# ui_xte_usb.net
KiCad netlist of a schematic drawn in Altium Designer
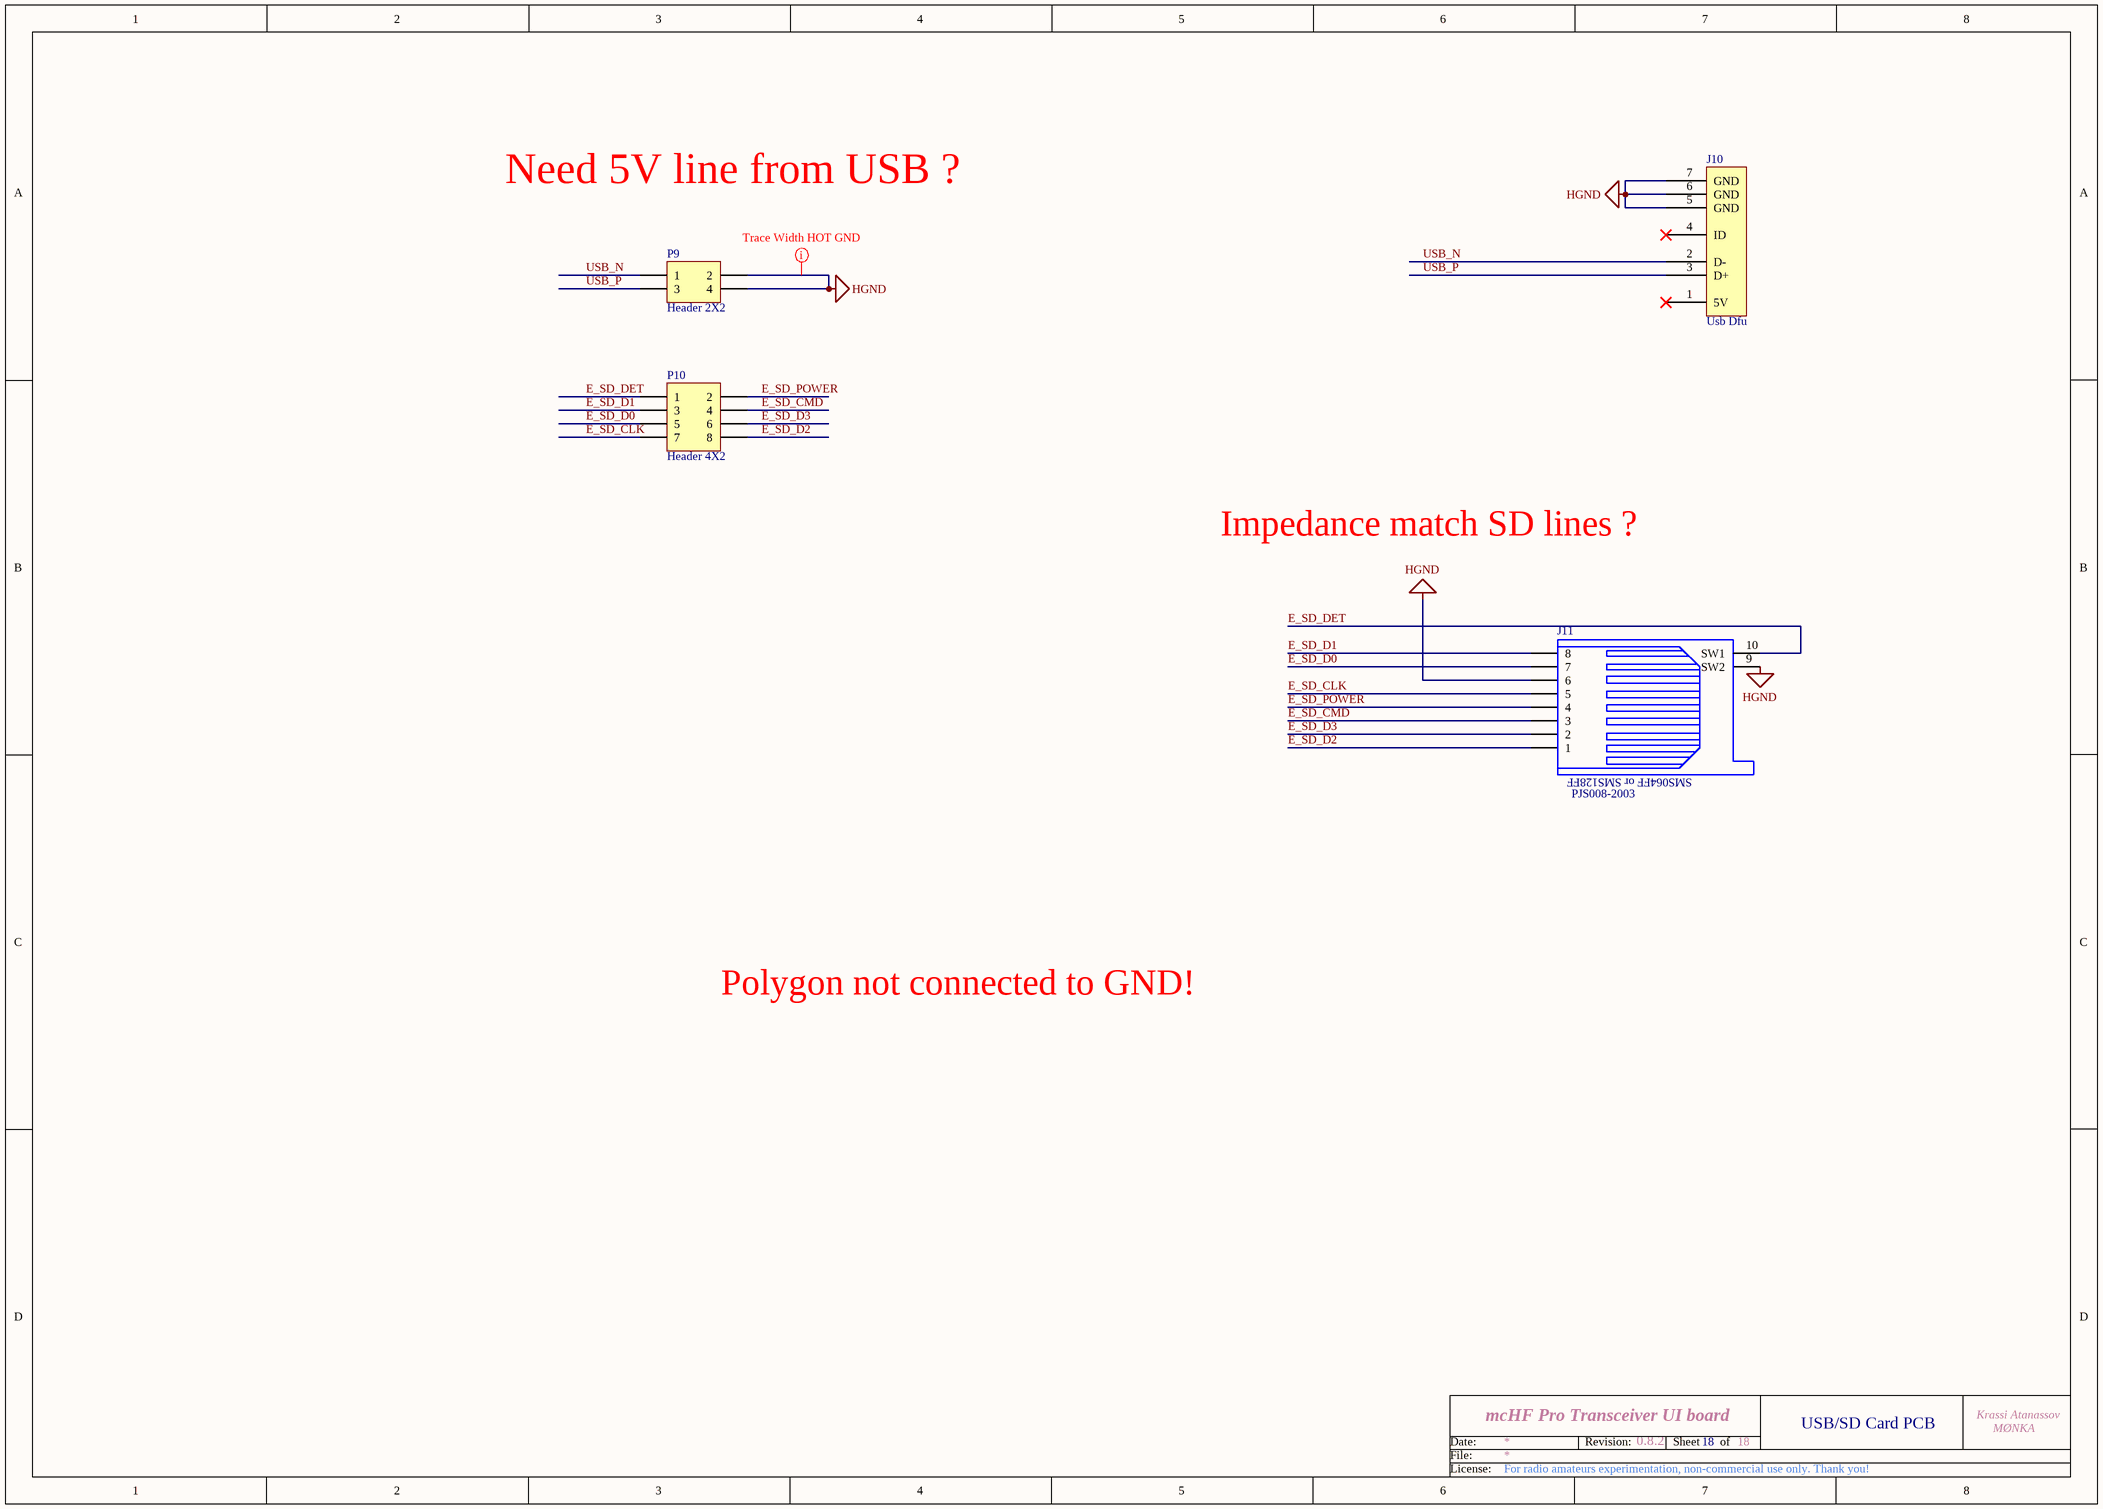
[diagram p0: ui_xte_usb.SchDoc]

(export (version "E")
  (design (tool "Eeschema 10.0.6"))
  (components
    (comp (ref "J10")
      (value "Usb Dfu")
      (footprint "MINI_USB_B_SMD")
      (description "Mini USB connector")
      (libsource (lib "mcHF_ui") (part "MINI_USB_B"))
    )
    (comp (ref "J11")
      (value "PJS008-2003")
      (footprint "PJS008-2003-1")
      (description "Memory Card Connectors MicroSD Card Conn Revrs Mnt Push-Push")
      (libsource (lib "MCD_TOOLS") (part "microSD-PJS008-2003"))
    )
    (comp (ref "P9")
      (value "Header 2X2")
      (footprint "HDR2X2R")
      (description "Header, 2-Pin, Dual row")
      (fields (field (name "PUBLISHER") "Altium Limited"))
      (libsource (lib "__ui") (part "Header 2X2"))
    )
    (comp (ref "P10")
      (value "Header 4X2")
      (footprint "HDR2X4R")
      (description "Header, 4-Pin, Dual row")
      (fields (field (name "PUBLISHER") "Altium Limited"))
      (libsource (lib "__ui") (part "Header 4X2"))
    )
  )
  (nets
    (net (code "1") (name "/E_SD_CLK") (class "Default")
      (node (ref "J11") (pin "5") (pinfunction "5_5") (pintype "passive"))
      (node (ref "P10") (pin "7") (pinfunction "7_7") (pintype "passive"))
    )
    (net (code "2") (name "/E_SD_CMD") (class "Default")
      (node (ref "J11") (pin "3") (pinfunction "3_3") (pintype "passive"))
      (node (ref "P10") (pin "4") (pinfunction "4_4") (pintype "passive"))
    )
    (net (code "3") (name "/E_SD_D0") (class "Default")
      (node (ref "J11") (pin "7") (pinfunction "7_7") (pintype "passive"))
      (node (ref "P10") (pin "5") (pinfunction "5_5") (pintype "passive"))
    )
    (net (code "4") (name "/E_SD_D1") (class "Default")
      (node (ref "J11") (pin "8") (pinfunction "8_8") (pintype "passive"))
      (node (ref "P10") (pin "3") (pinfunction "3_3") (pintype "passive"))
    )
    (net (code "5") (name "/E_SD_D2") (class "Default")
      (node (ref "J11") (pin "1") (pinfunction "1_1") (pintype "passive"))
      (node (ref "P10") (pin "8") (pinfunction "8_8") (pintype "passive"))
    )
    (net (code "6") (name "/E_SD_D3") (class "Default")
      (node (ref "J11") (pin "2") (pinfunction "2_2") (pintype "passive"))
      (node (ref "P10") (pin "6") (pinfunction "6_6") (pintype "passive"))
    )
    (net (code "7") (name "/E_SD_DET") (class "Default")
      (node (ref "J11") (pin "10") (pinfunction "SW1_10") (pintype "passive"))
      (node (ref "P10") (pin "1") (pinfunction "1_1") (pintype "passive"))
    )
    (net (code "8") (name "/E_SD_POWER") (class "Default")
      (node (ref "J11") (pin "4") (pinfunction "4_4") (pintype "passive"))
      (node (ref "P10") (pin "2") (pinfunction "2_2") (pintype "passive"))
    )
    (net (code "9") (name "/USB_N") (class "Default")
      (node (ref "J10") (pin "2") (pinfunction "D-_2") (pintype "passive"))
      (node (ref "P9") (pin "1") (pinfunction "1_1") (pintype "passive"))
    )
    (net (code "10") (name "/USB_P") (class "Default")
      (node (ref "J10") (pin "3") (pinfunction "D+_3") (pintype "passive"))
      (node (ref "P9") (pin "3") (pinfunction "3_3") (pintype "passive"))
    )
    (net (code "11") (name "HGND") (class "Default")
      (node (ref "J10") (pin "5") (pinfunction "GND_5") (pintype "passive"))
      (node (ref "J10") (pin "6") (pinfunction "GND_6") (pintype "passive"))
      (node (ref "J10") (pin "7") (pinfunction "GND_7") (pintype "passive"))
      (node (ref "J11") (pin "6") (pinfunction "6_6") (pintype "passive"))
      (node (ref "J11") (pin "9") (pinfunction "SW2_9") (pintype "passive"))
      (node (ref "P9") (pin "2") (pinfunction "2_2") (pintype "passive"))
      (node (ref "P9") (pin "4") (pinfunction "4_4") (pintype "passive"))
    )
    (net (code "12") (name "unconnected-(J10-5V-Pad1)") (class "Default")
      (node (ref "J10") (pin "1") (pinfunction "5V_1") (pintype "passive+no_connect"))
    )
    (net (code "13") (name "unconnected-(J10-ID-Pad4)") (class "Default")
      (node (ref "J10") (pin "4") (pinfunction "ID_4") (pintype "passive+no_connect"))
    )
  )
)
